# Master.net
KiCad netlist of a schematic drawn in EAGLE
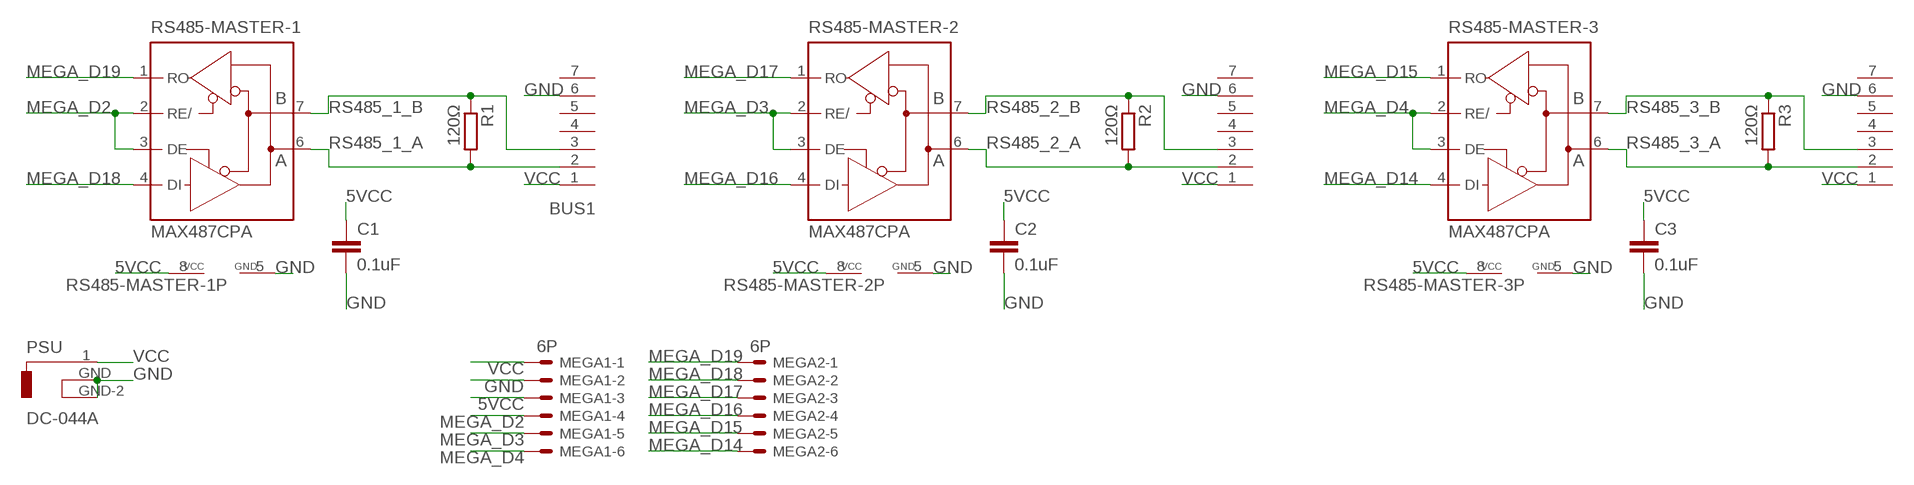
[diagram p0: schematic, sheet 1]

(export (version "E")
  (design (tool "Eeschema 10.0.6"))
  (components
    (comp (ref "BUS1")
      (value "GX12-7P")
      (footprint "eagle-import:GX12-7P")
      (libsource (lib "eagle-import") (part "GX12-7P"))
    )
    (comp (ref "BUS2")
      (value "GX12-7P")
      (footprint "eagle-import:GX12-7P")
      (libsource (lib "eagle-import") (part "GX12-7P"))
    )
    (comp (ref "BUS3")
      (value "GX12-7P")
      (footprint "eagle-import:GX12-7P")
      (libsource (lib "eagle-import") (part "GX12-7P"))
    )
    (comp (ref "C1")
      (value "0.1uF")
      (footprint "eagle-import:C025-025X050")
      (libsource (lib "eagle-import") (part "C-EU025-025X050"))
    )
    (comp (ref "C2")
      (value "0.1uF")
      (footprint "eagle-import:C025-025X050")
      (libsource (lib "eagle-import") (part "C-EU025-025X050"))
    )
    (comp (ref "C3")
      (value "0.1uF")
      (footprint "eagle-import:C025-025X050")
      (libsource (lib "eagle-import") (part "C-EU025-025X050"))
    )
    (comp (ref "MEGA1")
      (value "6P")
      (footprint "eagle-import:22-23-2061")
      (fields (field (name "MF") "MOLEX") (field (name "MPN") "22-23-2061"))
      (libsource (lib "eagle-import") (part "22-23-2061"))
    )
    (comp (ref "MEGA2")
      (value "6P")
      (footprint "eagle-import:22-23-2061")
      (fields (field (name "MF") "MOLEX") (field (name "MPN") "22-23-2061"))
      (libsource (lib "eagle-import") (part "22-23-2061"))
    )
    (comp (ref "PSU")
      (value "DC-044A")
      (footprint "eagle-import:DC-044A")
      (libsource (lib "eagle-import") (part "DC-044A"))
    )
    (comp (ref "R1")
      (value "120Ω")
      (footprint "eagle-import:0207_10")
      (libsource (lib "eagle-import") (part "R-EU_0207/10"))
    )
    (comp (ref "R2")
      (value "120Ω")
      (footprint "eagle-import:0207_10")
      (libsource (lib "eagle-import") (part "R-EU_0207/10"))
    )
    (comp (ref "R3")
      (value "120Ω")
      (footprint "eagle-import:0207_10")
      (libsource (lib "eagle-import") (part "R-EU_0207/10"))
    )
    (comp (ref "RS485-MASTER-1")
      (value "MAX487CPA")
      (footprint "eagle-import:DIL08")
      (libsource (lib "eagle-import") (part "MAX487CPA"))
    )
    (comp (ref "RS485-MASTER-2")
      (value "MAX487CPA")
      (footprint "eagle-import:DIL08")
      (libsource (lib "eagle-import") (part "MAX487CPA"))
    )
    (comp (ref "RS485-MASTER-3")
      (value "MAX487CPA")
      (footprint "eagle-import:DIL08")
      (libsource (lib "eagle-import") (part "MAX487CPA"))
    )
  )
  (nets
    (net (code "1") (name "/5VCC") (class "Default")
      (node (ref "C1") (pin "1") (pinfunction "1_1") (pintype "passive"))
      (node (ref "C2") (pin "1") (pinfunction "1_1") (pintype "passive"))
      (node (ref "C3") (pin "1") (pinfunction "1_1") (pintype "passive"))
      (node (ref "MEGA1") (pin "3") (pinfunction "S_3") (pintype "passive"))
      (node (ref "RS485-MASTER-1") (pin "8") (pinfunction "VCC_8") (pintype "power_in"))
      (node (ref "RS485-MASTER-2") (pin "8") (pinfunction "VCC_8") (pintype "power_in"))
      (node (ref "RS485-MASTER-3") (pin "8") (pinfunction "VCC_8") (pintype "power_in"))
    )
    (net (code "2") (name "/GND") (class "Default")
      (node (ref "BUS1") (pin "6") (pinfunction "6_6") (pintype "bidirectional"))
      (node (ref "BUS2") (pin "6") (pinfunction "6_6") (pintype "bidirectional"))
      (node (ref "BUS3") (pin "6") (pinfunction "6_6") (pintype "bidirectional"))
      (node (ref "C1") (pin "2") (pinfunction "2_2") (pintype "passive"))
      (node (ref "C2") (pin "2") (pinfunction "2_2") (pintype "passive"))
      (node (ref "C3") (pin "2") (pinfunction "2_2") (pintype "passive"))
      (node (ref "MEGA1") (pin "2") (pinfunction "S_2") (pintype "passive"))
      (node (ref "PSU") (pin "GND") (pinfunction "GND_GND") (pintype "power_in"))
      (node (ref "PSU") (pin "GND-2") (pinfunction "GND-2_GND-2") (pintype "power_in"))
      (node (ref "RS485-MASTER-1") (pin "5") (pinfunction "GND_5") (pintype "power_in"))
      (node (ref "RS485-MASTER-2") (pin "5") (pinfunction "GND_5") (pintype "power_in"))
      (node (ref "RS485-MASTER-3") (pin "5") (pinfunction "GND_5") (pintype "power_in"))
    )
    (net (code "3") (name "/MEGA_D2") (class "Default")
      (node (ref "MEGA1") (pin "4") (pinfunction "S_4") (pintype "passive"))
      (node (ref "RS485-MASTER-1") (pin "2") (pinfunction "RE/_2") (pintype "input"))
      (node (ref "RS485-MASTER-1") (pin "3") (pinfunction "DE_3") (pintype "input"))
    )
    (net (code "4") (name "/MEGA_D3") (class "Default")
      (node (ref "MEGA1") (pin "5") (pinfunction "S_5") (pintype "passive"))
      (node (ref "RS485-MASTER-2") (pin "2") (pinfunction "RE/_2") (pintype "input"))
      (node (ref "RS485-MASTER-2") (pin "3") (pinfunction "DE_3") (pintype "input"))
    )
    (net (code "5") (name "/MEGA_D4") (class "Default")
      (node (ref "MEGA1") (pin "6") (pinfunction "S_6") (pintype "passive"))
      (node (ref "RS485-MASTER-3") (pin "2") (pinfunction "RE/_2") (pintype "input"))
      (node (ref "RS485-MASTER-3") (pin "3") (pinfunction "DE_3") (pintype "input"))
    )
    (net (code "6") (name "/MEGA_D14") (class "Default")
      (node (ref "MEGA2") (pin "6") (pinfunction "S_6") (pintype "passive"))
      (node (ref "RS485-MASTER-3") (pin "4") (pinfunction "DI_4") (pintype "input"))
    )
    (net (code "7") (name "/MEGA_D15") (class "Default")
      (node (ref "MEGA2") (pin "5") (pinfunction "S_5") (pintype "passive"))
      (node (ref "RS485-MASTER-3") (pin "1") (pinfunction "RO_1") (pintype "output"))
    )
    (net (code "8") (name "/MEGA_D16") (class "Default")
      (node (ref "MEGA2") (pin "4") (pinfunction "S_4") (pintype "passive"))
      (node (ref "RS485-MASTER-2") (pin "4") (pinfunction "DI_4") (pintype "input"))
    )
    (net (code "9") (name "/MEGA_D17") (class "Default")
      (node (ref "MEGA2") (pin "3") (pinfunction "S_3") (pintype "passive"))
      (node (ref "RS485-MASTER-2") (pin "1") (pinfunction "RO_1") (pintype "output"))
    )
    (net (code "10") (name "/MEGA_D18") (class "Default")
      (node (ref "MEGA2") (pin "2") (pinfunction "S_2") (pintype "passive"))
      (node (ref "RS485-MASTER-1") (pin "4") (pinfunction "DI_4") (pintype "input"))
    )
    (net (code "11") (name "/MEGA_D19") (class "Default")
      (node (ref "MEGA2") (pin "1") (pinfunction "S_1") (pintype "passive"))
      (node (ref "RS485-MASTER-1") (pin "1") (pinfunction "RO_1") (pintype "output"))
    )
    (net (code "12") (name "/RS485_1_A") (class "Default")
      (node (ref "BUS1") (pin "2") (pinfunction "2_2") (pintype "bidirectional"))
      (node (ref "R1") (pin "2") (pinfunction "2_2") (pintype "passive"))
      (node (ref "RS485-MASTER-1") (pin "6") (pinfunction "A_6") (pintype "passive"))
    )
    (net (code "13") (name "/RS485_1_B") (class "Default")
      (node (ref "BUS1") (pin "3") (pinfunction "3_3") (pintype "bidirectional"))
      (node (ref "R1") (pin "1") (pinfunction "1_1") (pintype "passive"))
      (node (ref "RS485-MASTER-1") (pin "7") (pinfunction "B_7") (pintype "passive"))
    )
    (net (code "14") (name "/RS485_2_A") (class "Default")
      (node (ref "BUS2") (pin "2") (pinfunction "2_2") (pintype "bidirectional"))
      (node (ref "R2") (pin "2") (pinfunction "2_2") (pintype "passive"))
      (node (ref "RS485-MASTER-2") (pin "6") (pinfunction "A_6") (pintype "passive"))
    )
    (net (code "15") (name "/RS485_2_B") (class "Default")
      (node (ref "BUS2") (pin "3") (pinfunction "3_3") (pintype "bidirectional"))
      (node (ref "R2") (pin "1") (pinfunction "1_1") (pintype "passive"))
      (node (ref "RS485-MASTER-2") (pin "7") (pinfunction "B_7") (pintype "passive"))
    )
    (net (code "16") (name "/RS485_3_A") (class "Default")
      (node (ref "BUS3") (pin "2") (pinfunction "2_2") (pintype "bidirectional"))
      (node (ref "R3") (pin "2") (pinfunction "2_2") (pintype "passive"))
      (node (ref "RS485-MASTER-3") (pin "6") (pinfunction "A_6") (pintype "passive"))
    )
    (net (code "17") (name "/RS485_3_B") (class "Default")
      (node (ref "BUS3") (pin "3") (pinfunction "3_3") (pintype "bidirectional"))
      (node (ref "R3") (pin "1") (pinfunction "1_1") (pintype "passive"))
      (node (ref "RS485-MASTER-3") (pin "7") (pinfunction "B_7") (pintype "passive"))
    )
    (net (code "18") (name "/VCC") (class "Default")
      (node (ref "BUS1") (pin "1") (pinfunction "1_1") (pintype "bidirectional"))
      (node (ref "BUS2") (pin "1") (pinfunction "1_1") (pintype "bidirectional"))
      (node (ref "BUS3") (pin "1") (pinfunction "1_1") (pintype "bidirectional"))
      (node (ref "MEGA1") (pin "1") (pinfunction "S_1") (pintype "passive"))
      (node (ref "PSU") (pin "1") (pinfunction "1_1") (pintype "power_in"))
    )
    (net (code "19") (name "unconnected-(BUS1-Pad4)") (class "Default")
      (node (ref "BUS1") (pin "4") (pinfunction "4_4") (pintype "bidirectional"))
    )
    (net (code "20") (name "unconnected-(BUS1-Pad5)") (class "Default")
      (node (ref "BUS1") (pin "5") (pinfunction "5_5") (pintype "bidirectional"))
    )
    (net (code "21") (name "unconnected-(BUS1-Pad7)") (class "Default")
      (node (ref "BUS1") (pin "7") (pinfunction "7_7") (pintype "bidirectional"))
    )
    (net (code "22") (name "unconnected-(BUS2-Pad4)") (class "Default")
      (node (ref "BUS2") (pin "4") (pinfunction "4_4") (pintype "bidirectional"))
    )
    (net (code "23") (name "unconnected-(BUS2-Pad5)") (class "Default")
      (node (ref "BUS2") (pin "5") (pinfunction "5_5") (pintype "bidirectional"))
    )
    (net (code "24") (name "unconnected-(BUS2-Pad7)") (class "Default")
      (node (ref "BUS2") (pin "7") (pinfunction "7_7") (pintype "bidirectional"))
    )
    (net (code "25") (name "unconnected-(BUS3-Pad4)") (class "Default")
      (node (ref "BUS3") (pin "4") (pinfunction "4_4") (pintype "bidirectional"))
    )
    (net (code "26") (name "unconnected-(BUS3-Pad5)") (class "Default")
      (node (ref "BUS3") (pin "5") (pinfunction "5_5") (pintype "bidirectional"))
    )
    (net (code "27") (name "unconnected-(BUS3-Pad7)") (class "Default")
      (node (ref "BUS3") (pin "7") (pinfunction "7_7") (pintype "bidirectional"))
    )
  )
)
